# 06_JTAG_DBUG.net
KiCad netlist of a schematic drawn in Altium Designer
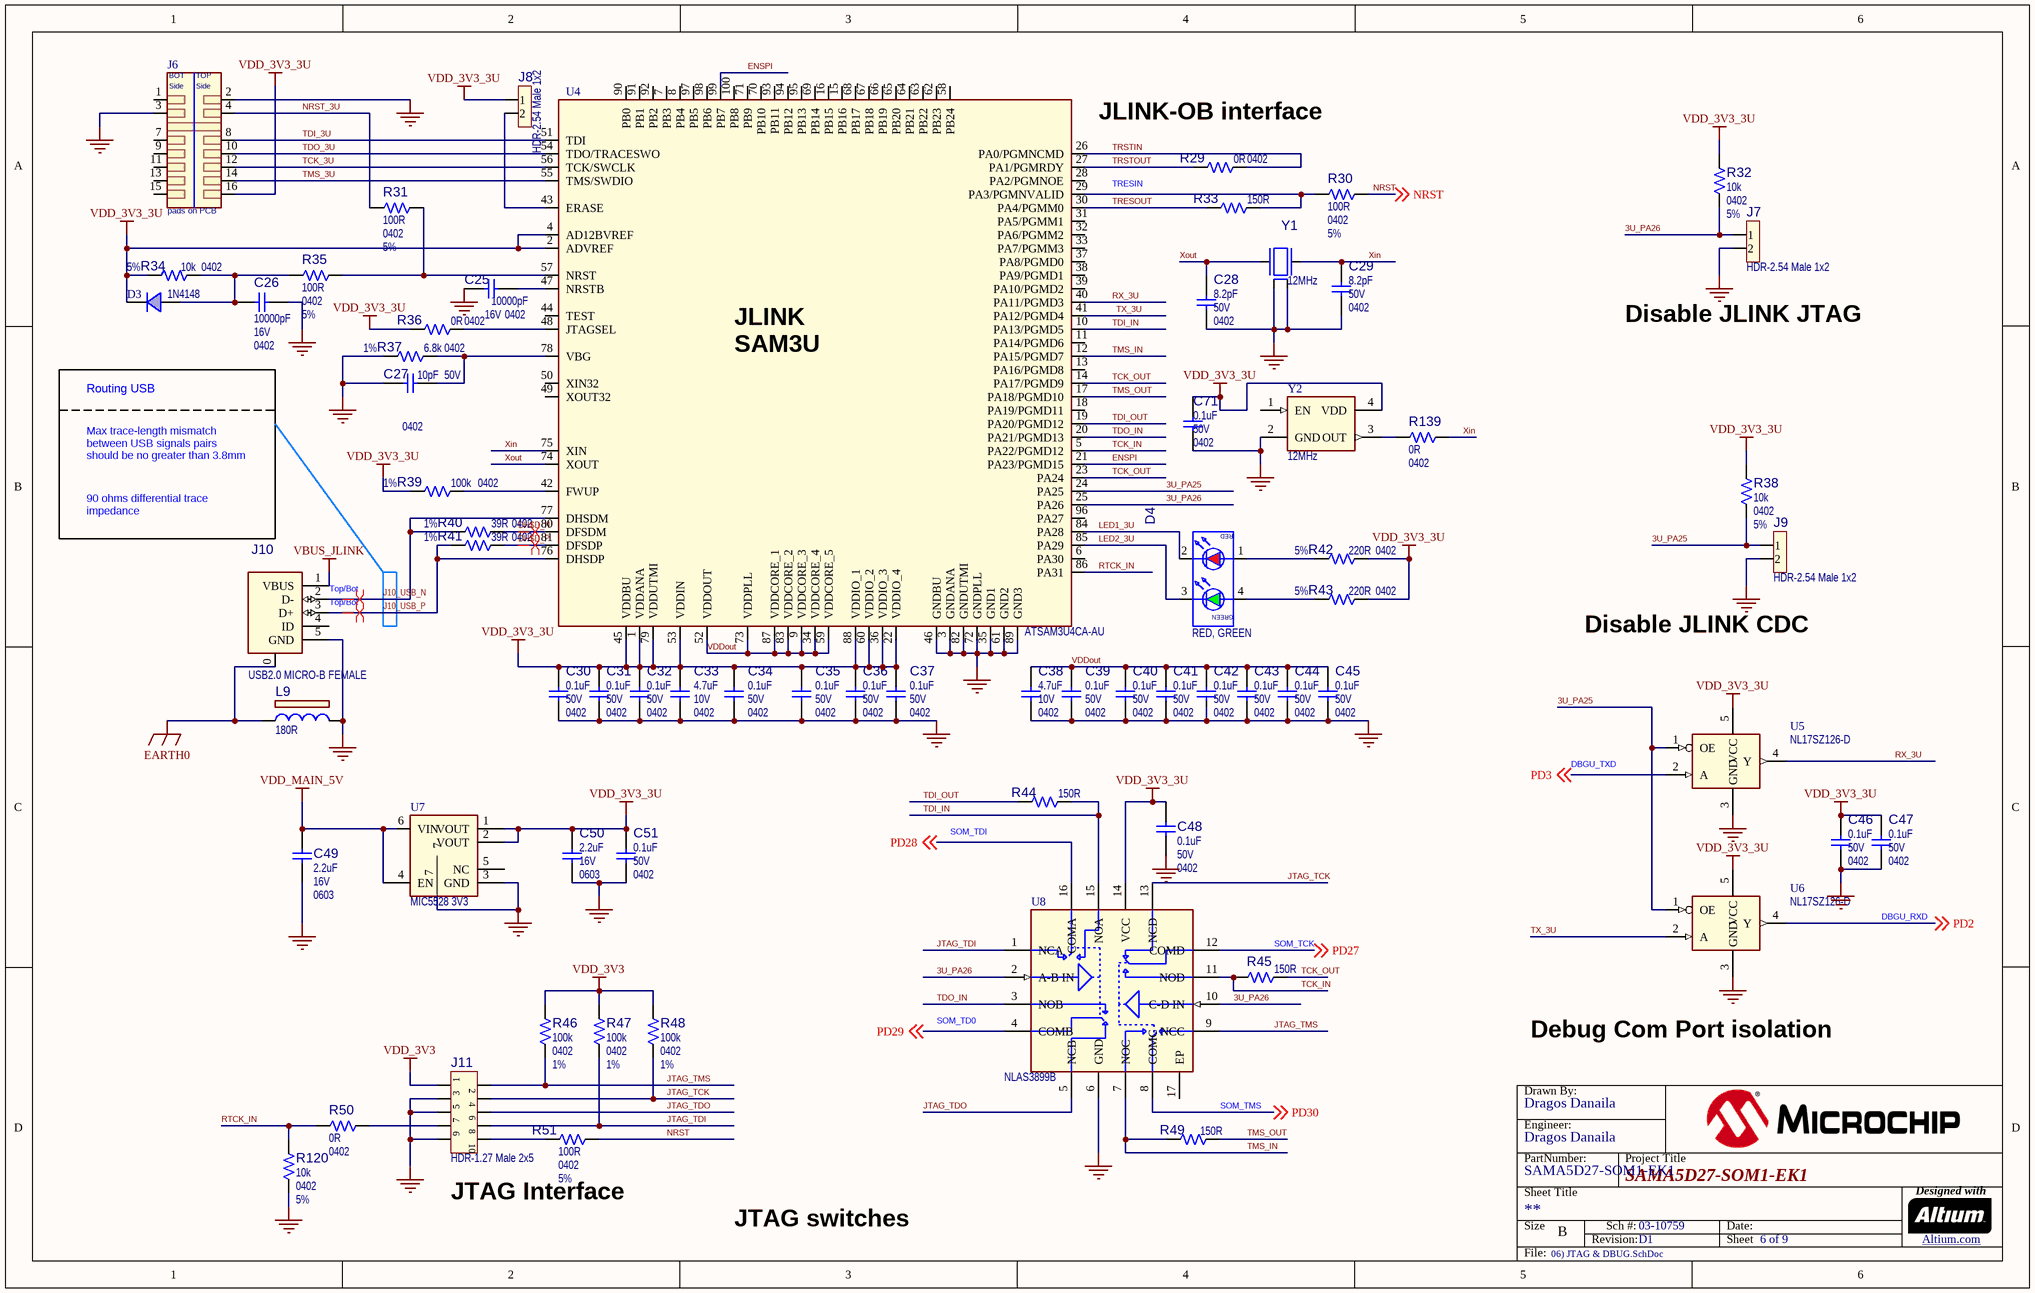
[diagram p0: 06) JTAG & DBUG.SchDoc]

(export (version "E")
  (design (tool "Eeschema 10.0.6"))
  (components
    (comp (ref "C25")
      (value "10000pF")
      (footprint "CAP_C_0402")
      (description "Capacitor")
      (fields
        (field (name "VOLTAGE") "16V")
        (field (name "PACKAGE") "0402")
        (field (name "TOLERANCE") "10%")
        (field (name "Comment") "Capacitor NP")
      )
      (libsource (lib "MCHP-CDB") (part "Capacitor NP"))
    )
    (comp (ref "C26")
      (value "10000pF")
      (footprint "CAP_C_0402")
      (description "Capacitor")
      (fields
        (field (name "VOLTAGE") "16V")
        (field (name "PACKAGE") "0402")
        (field (name "TOLERANCE") "10%")
        (field (name "Comment") "Capacitor NP")
      )
      (libsource (lib "MCHP-CDB") (part "Capacitor NP"))
    )
    (comp (ref "C27")
      (value "10pF")
      (footprint "CAP_C_0402")
      (description "Capacitor")
      (fields
        (field (name "VOLTAGE") "50V")
        (field (name "PACKAGE") "0402")
        (field (name "TOLERANCE") "5%")
        (field (name "Comment") "Capacitor NP")
      )
      (libsource (lib "MCHP-CDB") (part "Capacitor NP"))
    )
    (comp (ref "C28")
      (value "8.2pF")
      (footprint "CAP_C_0402")
      (description "Capacitor")
      (fields
        (field (name "VOLTAGE") "50V")
        (field (name "PACKAGE") "0402")
        (field (name "TOLERANCE") "0.25pF")
        (field (name "Comment") "Capacitor NP")
        (field (name "OWNER") "Gabor Bihari")
      )
      (libsource (lib "MCHP-CDB") (part "Capacitor NP"))
    )
    (comp (ref "C29")
      (value "8.2pF")
      (footprint "CAP_C_0402")
      (description "Capacitor")
      (fields
        (field (name "VOLTAGE") "50V")
        (field (name "PACKAGE") "0402")
        (field (name "TOLERANCE") "0.25pF")
        (field (name "Comment") "Capacitor NP")
        (field (name "OWNER") "Gabor Bihari")
      )
      (libsource (lib "MCHP-CDB") (part "Capacitor NP"))
    )
    (comp (ref "C30")
      (value "0.1uF")
      (footprint "CAP_C_0402")
      (description "Capacitor")
      (fields
        (field (name "VOLTAGE") "50V")
        (field (name "PACKAGE") "0402")
        (field (name "TOLERANCE") "10%")
        (field (name "Comment") "Capacitor NP")
        (field (name "OWNER") "Jamus Griego")
      )
      (libsource (lib "MCHP-CDB") (part "Capacitor NP"))
    )
    (comp (ref "C31")
      (value "0.1uF")
      (footprint "CAP_C_0402")
      (description "Capacitor")
      (fields
        (field (name "VOLTAGE") "50V")
        (field (name "PACKAGE") "0402")
        (field (name "TOLERANCE") "10%")
        (field (name "Comment") "Capacitor NP")
        (field (name "OWNER") "Jamus Griego")
      )
      (libsource (lib "MCHP-CDB") (part "Capacitor NP"))
    )
    (comp (ref "C32")
      (value "0.1uF")
      (footprint "CAP_C_0402")
      (description "Capacitor")
      (fields
        (field (name "VOLTAGE") "50V")
        (field (name "PACKAGE") "0402")
        (field (name "TOLERANCE") "10%")
        (field (name "Comment") "Capacitor NP")
        (field (name "OWNER") "Jamus Griego")
      )
      (libsource (lib "MCHP-CDB") (part "Capacitor NP"))
    )
    (comp (ref "C33")
      (value "4.7uF")
      (footprint "CAP_C_0402")
      (description "Capacitor")
      (fields
        (field (name "VOLTAGE") "10V")
        (field (name "PACKAGE") "0402")
        (field (name "TOLERANCE") "10%")
        (field (name "Comment") "Capacitor NP")
        (field (name "OWNER") "Jesus Aviles")
      )
      (libsource (lib "MCHP-CDB") (part "Capacitor NP"))
    )
    (comp (ref "C34")
      (value "0.1uF")
      (footprint "CAP_C_0402")
      (description "Capacitor")
      (fields
        (field (name "VOLTAGE") "50V")
        (field (name "PACKAGE") "0402")
        (field (name "TOLERANCE") "10%")
        (field (name "Comment") "Capacitor NP")
        (field (name "OWNER") "Jamus Griego")
      )
      (libsource (lib "MCHP-CDB") (part "Capacitor NP"))
    )
    (comp (ref "C35")
      (value "0.1uF")
      (footprint "CAP_C_0402")
      (description "Capacitor")
      (fields
        (field (name "VOLTAGE") "50V")
        (field (name "PACKAGE") "0402")
        (field (name "TOLERANCE") "10%")
        (field (name "Comment") "Capacitor NP")
        (field (name "OWNER") "Jamus Griego")
      )
      (libsource (lib "MCHP-CDB") (part "Capacitor NP"))
    )
    (comp (ref "C36")
      (value "0.1uF")
      (footprint "CAP_C_0402")
      (description "Capacitor")
      (fields
        (field (name "VOLTAGE") "50V")
        (field (name "PACKAGE") "0402")
        (field (name "TOLERANCE") "10%")
        (field (name "Comment") "Capacitor NP")
        (field (name "OWNER") "Jamus Griego")
      )
      (libsource (lib "MCHP-CDB") (part "Capacitor NP"))
    )
    (comp (ref "C37")
      (value "0.1uF")
      (footprint "CAP_C_0402")
      (description "Capacitor")
      (fields
        (field (name "VOLTAGE") "50V")
        (field (name "PACKAGE") "0402")
        (field (name "TOLERANCE") "10%")
        (field (name "Comment") "Capacitor NP")
        (field (name "OWNER") "Jamus Griego")
      )
      (libsource (lib "MCHP-CDB") (part "Capacitor NP"))
    )
    (comp (ref "C38")
      (value "4.7uF")
      (footprint "CAP_C_0402")
      (description "Capacitor")
      (fields
        (field (name "VOLTAGE") "10V")
        (field (name "PACKAGE") "0402")
        (field (name "TOLERANCE") "10%")
        (field (name "Comment") "Capacitor NP")
        (field (name "OWNER") "Jesus Aviles")
      )
      (libsource (lib "MCHP-CDB") (part "Capacitor NP"))
    )
    (comp (ref "C39")
      (value "0.1uF")
      (footprint "CAP_C_0402")
      (description "Capacitor")
      (fields
        (field (name "VOLTAGE") "50V")
        (field (name "PACKAGE") "0402")
        (field (name "TOLERANCE") "10%")
        (field (name "Comment") "Capacitor NP")
        (field (name "OWNER") "Jamus Griego")
      )
      (libsource (lib "MCHP-CDB") (part "Capacitor NP"))
    )
    (comp (ref "C40")
      (value "0.1uF")
      (footprint "CAP_C_0402")
      (description "Capacitor")
      (fields
        (field (name "VOLTAGE") "50V")
        (field (name "PACKAGE") "0402")
        (field (name "TOLERANCE") "10%")
        (field (name "Comment") "Capacitor NP")
        (field (name "OWNER") "Jamus Griego")
      )
      (libsource (lib "MCHP-CDB") (part "Capacitor NP"))
    )
    (comp (ref "C41")
      (value "0.1uF")
      (footprint "CAP_C_0402")
      (description "Capacitor")
      (fields
        (field (name "VOLTAGE") "50V")
        (field (name "PACKAGE") "0402")
        (field (name "TOLERANCE") "10%")
        (field (name "Comment") "Capacitor NP")
        (field (name "OWNER") "Jamus Griego")
      )
      (libsource (lib "MCHP-CDB") (part "Capacitor NP"))
    )
    (comp (ref "C42")
      (value "0.1uF")
      (footprint "CAP_C_0402")
      (description "Capacitor")
      (fields
        (field (name "VOLTAGE") "50V")
        (field (name "PACKAGE") "0402")
        (field (name "TOLERANCE") "10%")
        (field (name "Comment") "Capacitor NP")
        (field (name "OWNER") "Jamus Griego")
      )
      (libsource (lib "MCHP-CDB") (part "Capacitor NP"))
    )
    (comp (ref "C43")
      (value "0.1uF")
      (footprint "CAP_C_0402")
      (description "Capacitor")
      (fields
        (field (name "VOLTAGE") "50V")
        (field (name "PACKAGE") "0402")
        (field (name "TOLERANCE") "10%")
        (field (name "Comment") "Capacitor NP")
        (field (name "OWNER") "Jamus Griego")
      )
      (libsource (lib "MCHP-CDB") (part "Capacitor NP"))
    )
    (comp (ref "C44")
      (value "0.1uF")
      (footprint "CAP_C_0402")
      (description "Capacitor")
      (fields
        (field (name "VOLTAGE") "50V")
        (field (name "PACKAGE") "0402")
        (field (name "TOLERANCE") "10%")
        (field (name "Comment") "Capacitor NP")
        (field (name "OWNER") "Jamus Griego")
      )
      (libsource (lib "MCHP-CDB") (part "Capacitor NP"))
    )
    (comp (ref "C45")
      (value "0.1uF")
      (footprint "CAP_C_0402")
      (description "Capacitor")
      (fields
        (field (name "VOLTAGE") "50V")
        (field (name "PACKAGE") "0402")
        (field (name "TOLERANCE") "10%")
        (field (name "Comment") "Capacitor NP")
        (field (name "OWNER") "Jamus Griego")
      )
      (libsource (lib "MCHP-CDB") (part "Capacitor NP"))
    )
    (comp (ref "C46")
      (value "0.1uF")
      (footprint "CAP_C_0402")
      (description "Capacitor")
      (fields
        (field (name "VOLTAGE") "50V")
        (field (name "PACKAGE") "0402")
        (field (name "TOLERANCE") "10%")
        (field (name "Comment") "Capacitor NP")
        (field (name "OWNER") "Jamus Griego")
      )
      (libsource (lib "MCHP-CDB") (part "Capacitor NP"))
    )
    (comp (ref "C47")
      (value "0.1uF")
      (footprint "CAP_C_0402")
      (description "Capacitor")
      (fields
        (field (name "VOLTAGE") "50V")
        (field (name "PACKAGE") "0402")
        (field (name "TOLERANCE") "10%")
        (field (name "Comment") "Capacitor NP")
        (field (name "OWNER") "Jamus Griego")
      )
      (libsource (lib "MCHP-CDB") (part "Capacitor NP"))
    )
    (comp (ref "C48")
      (value "0.1uF")
      (footprint "CAP_C_0402")
      (description "Capacitor")
      (fields
        (field (name "VOLTAGE") "50V")
        (field (name "PACKAGE") "0402")
        (field (name "TOLERANCE") "10%")
        (field (name "Comment") "Capacitor NP")
        (field (name "OWNER") "Jamus Griego")
      )
      (libsource (lib "MCHP-CDB") (part "Capacitor NP"))
    )
    (comp (ref "C49")
      (value "2.2uF")
      (footprint "CAP_C_0603")
      (description "Capacitor")
      (fields
        (field (name "VOLTAGE") "16V")
        (field (name "PACKAGE") "0603")
        (field (name "TOLERANCE") "10%")
        (field (name "Comment") "Capacitor NP")
      )
      (libsource (lib "MCHP-CDB") (part "Capacitor NP"))
    )
    (comp (ref "C50")
      (value "2.2uF")
      (footprint "CAP_C_0603")
      (description "Capacitor")
      (fields
        (field (name "VOLTAGE") "16V")
        (field (name "PACKAGE") "0603")
        (field (name "TOLERANCE") "10%")
        (field (name "Comment") "Capacitor NP")
      )
      (libsource (lib "MCHP-CDB") (part "Capacitor NP"))
    )
    (comp (ref "C51")
      (value "0.1uF")
      (footprint "CAP_C_0402")
      (description "Capacitor")
      (fields
        (field (name "VOLTAGE") "50V")
        (field (name "PACKAGE") "0402")
        (field (name "TOLERANCE") "10%")
        (field (name "Comment") "Capacitor NP")
        (field (name "OWNER") "Jamus Griego")
      )
      (libsource (lib "MCHP-CDB") (part "Capacitor NP"))
    )
    (comp (ref "C71")
      (value "0.1uF")
      (footprint "CAP_C_0402")
      (description "Capacitor")
      (fields
        (field (name "VOLTAGE") "50V")
        (field (name "PACKAGE") "0402")
        (field (name "TOLERANCE") "10%")
        (field (name "Comment") "Capacitor NP")
        (field (name "OWNER") "Jamus Griego")
      )
      (libsource (lib "MCHP-CDB") (part "Capacitor NP"))
    )
    (comp (ref "D3")
      (value "1N4148")
      (footprint "SOD-323")
      (description "DIO RECT 1N4148 855mV 300mA 75V SOD-323")
      (fields (field (name "POWER") "200mW") (field (name "Comment") "Diode Single"))
      (libsource (lib "MCHP-CDB") (part "Diode Single"))
    )
    (comp (ref "D4")
      (value "RED, GREEN")
      (footprint "LED_DUAL_SMD_2x1.25mm")
      (description "LED")
      (fields
        (field (name "POWER") "75mW")
        (field (name "Comment") "LED DUAL 4 pin")
        (field (name "OWNER") "Bogdan P (M91398)")
      )
      (libsource (lib "MCHP-CDB") (part "LED DUAL 4 pin"))
    )
    (comp (ref "J6")
      (value "pads on PCB")
      (footprint "CON_EDGE-CARD_PCB_RA_MEC1-108-02-F-D-RA1-SL")
      (description "CON_PCB_MEC1-108-02-F-D-RA1-SL")
      (fields (field (name "OWNER") "Dragos Danaila"))
      (libsource (lib "MCHP-CDB") (part "CON_PCB_MEC1-108-02-F-D-RA1-SL"))
    )
    (comp (ref "J7")
      (value "HDR-2.54 Male 1x2")
      (footprint "HDR_M_2.54_1x2")
      (fields (field (name "Comment") "Header 1x2") (field (name "OWNER") "Bogdan P (M91398)"))
      (libsource (lib "MCHP-CDB") (part "Header 1x2"))
    )
    (comp (ref "J8")
      (value "HDR-2.54 Male 1x2")
      (footprint "HDR_M_2.54_1x2")
      (fields (field (name "Comment") "Header 1x2") (field (name "OWNER") "Bogdan P (M91398)"))
      (libsource (lib "MCHP-CDB") (part "Header 1x2"))
    )
    (comp (ref "J9")
      (value "HDR-2.54 Male 1x2")
      (footprint "HDR_M_2.54_1x2")
      (fields (field (name "Comment") "Header 1x2") (field (name "OWNER") "Bogdan P (M91398)"))
      (libsource (lib "MCHP-CDB") (part "Header 1x2"))
    )
    (comp (ref "J10")
      (value "USB2.0 MICRO-B FEMALE")
      (footprint "CON_USB_Micro-AB_SMD_TH_RA_FCI_10118194-0001LF")
      (description "Connector USB Mini")
      (fields (field (name "Comment") "CON USB2.0 Mini_Micro") (field (name "OWNER") "Jamus Griego"))
      (libsource (lib "MCHP-CDB") (part "CON USB2.0 Mini_Micro"))
    )
    (comp (ref "J11")
      (value "HDR-1.27 Male 2x5")
      (footprint "HDR_M_1.27_2x5_SMD_V_SAM_FTSH-105-01-F-DV-K")
      (description "CON HDR-1.27 Male 2x5 Gold 3.05MH SMD VERT")
      (fields (field (name "Comment") "Header 2x5") (field (name "OWNER") "Tad Ahlvers"))
      (libsource (lib "MCHP-CDB") (part "Header 2x5"))
    )
    (comp (ref "L9")
      (value "180R")
      (footprint "IND_C_0603")
      (description "FERRITE 180R 1.5A SMD 0603")
      (fields (field (name "Comment") "Ferrite Bead") (field (name "OWNER") "Dragos Danaila"))
      (libsource (lib "MCHP-CDB") (part "Ferrite Bead"))
    )
    (comp (ref "R29")
      (value "0R")
      (footprint "RES_C_0402")
      (description "Resistor")
      (fields (field (name "PACKAGE") "0402") (field (name "POWER") "1/10W"))
      (libsource (lib "MCHP-CDB") (part "Resistor"))
    )
    (comp (ref "R30")
      (value "100R")
      (footprint "RES_C_0402")
      (description "Resistor")
      (fields
        (field (name "PACKAGE") "0402")
        (field (name "TOLERANCE") "5%")
        (field (name "VOLTAGE") "50V")
        (field (name "POWER") "1/16W")
        (field (name "OWNER") "Sompoch Loboonlert")
      )
      (libsource (lib "MCHP-CDB") (part "Resistor"))
    )
    (comp (ref "R31")
      (value "100R")
      (footprint "RES_C_0402")
      (description "Resistor")
      (fields
        (field (name "PACKAGE") "0402")
        (field (name "TOLERANCE") "5%")
        (field (name "VOLTAGE") "50V")
        (field (name "POWER") "1/16W")
        (field (name "OWNER") "Sompoch Loboonlert")
      )
      (libsource (lib "MCHP-CDB") (part "Resistor"))
    )
    (comp (ref "R32")
      (value "10k")
      (footprint "RES_C_0402")
      (description "Resistor")
      (fields
        (field (name "PACKAGE") "0402")
        (field (name "TOLERANCE") "5%")
        (field (name "VOLTAGE") "50V")
        (field (name "POWER") "1/16W")
      )
      (libsource (lib "MCHP-CDB") (part "Resistor"))
    )
    (comp (ref "R33")
      (value "150R")
      (footprint "RES_C_0402")
      (description "Resistor")
      (fields (field (name "OWNER") "Jamus Griego"))
      (libsource (lib "MCHP-CDB") (part "Resistor"))
    )
    (comp (ref "R34")
      (value "10k")
      (footprint "RES_C_0402")
      (description "Resistor")
      (fields
        (field (name "PACKAGE") "0402")
        (field (name "TOLERANCE") "5%")
        (field (name "VOLTAGE") "50V")
        (field (name "POWER") "1/16W")
      )
      (libsource (lib "MCHP-CDB") (part "Resistor"))
    )
    (comp (ref "R35")
      (value "100R")
      (footprint "RES_C_0402")
      (description "Resistor")
      (fields
        (field (name "PACKAGE") "0402")
        (field (name "TOLERANCE") "5%")
        (field (name "VOLTAGE") "50V")
        (field (name "POWER") "1/16W")
        (field (name "OWNER") "Sompoch Loboonlert")
      )
      (libsource (lib "MCHP-CDB") (part "Resistor"))
    )
    (comp (ref "R36")
      (value "0R")
      (footprint "RES_C_0402")
      (description "Resistor")
      (fields (field (name "PACKAGE") "0402") (field (name "POWER") "1/10W"))
      (libsource (lib "MCHP-CDB") (part "Resistor"))
    )
    (comp (ref "R37")
      (value "6.8k")
      (footprint "RES_C_0402")
      (description "Resistor")
      (fields
        (field (name "PACKAGE") "0402")
        (field (name "TOLERANCE") "1%")
        (field (name "VOLTAGE") "50V")
        (field (name "POWER") "1/16W")
        (field (name "OWNER") "Dragos Danaila")
      )
      (libsource (lib "MCHP-CDB") (part "Resistor"))
    )
    (comp (ref "R38")
      (value "10k")
      (footprint "RES_C_0402")
      (description "Resistor")
      (fields
        (field (name "PACKAGE") "0402")
        (field (name "TOLERANCE") "5%")
        (field (name "VOLTAGE") "50V")
        (field (name "POWER") "1/16W")
      )
      (libsource (lib "MCHP-CDB") (part "Resistor"))
    )
    (comp (ref "R39")
      (value "100k")
      (footprint "RES_C_0402")
      (description "Resistor")
      (fields
        (field (name "PACKAGE") "0402")
        (field (name "TOLERANCE") "1%")
        (field (name "VOLTAGE") "50V")
        (field (name "POWER") "1/10W")
        (field (name "OWNER") "Tad Ahlvers")
      )
      (libsource (lib "MCHP-CDB") (part "Resistor"))
    )
    (comp (ref "R40")
      (value "39R")
      (footprint "RES_C_0402")
      (description "Resistor")
      (fields
        (field (name "PACKAGE") "0402")
        (field (name "TOLERANCE") "1%")
        (field (name "POWER") "1/16W")
        (field (name "OWNER") "Sompoch Loboonlert")
      )
      (libsource (lib "MCHP-CDB") (part "Resistor"))
    )
    (comp (ref "R41")
      (value "39R")
      (footprint "RES_C_0402")
      (description "Resistor")
      (fields
        (field (name "PACKAGE") "0402")
        (field (name "TOLERANCE") "1%")
        (field (name "POWER") "1/16W")
        (field (name "OWNER") "Sompoch Loboonlert")
      )
      (libsource (lib "MCHP-CDB") (part "Resistor"))
    )
    (comp (ref "R42")
      (value "220R")
      (footprint "RES_C_0402")
      (description "Resistor")
      (fields
        (field (name "PACKAGE") "0402")
        (field (name "TOLERANCE") "5%")
        (field (name "VOLTAGE") "50V")
        (field (name "POWER") "1/10W")
        (field (name "OWNER") "Tad Ahlvers")
      )
      (libsource (lib "MCHP-CDB") (part "Resistor"))
    )
    (comp (ref "R43")
      (value "220R")
      (footprint "RES_C_0402")
      (description "Resistor")
      (fields
        (field (name "PACKAGE") "0402")
        (field (name "TOLERANCE") "5%")
        (field (name "VOLTAGE") "50V")
        (field (name "POWER") "1/10W")
        (field (name "OWNER") "Tad Ahlvers")
      )
      (libsource (lib "MCHP-CDB") (part "Resistor"))
    )
    (comp (ref "R44")
      (value "150R")
      (footprint "RES_C_0402")
      (description "Resistor")
      (fields (field (name "OWNER") "Jamus Griego"))
      (libsource (lib "MCHP-CDB") (part "Resistor"))
    )
    (comp (ref "R45")
      (value "150R")
      (footprint "RES_C_0402")
      (description "Resistor")
      (fields (field (name "OWNER") "Jamus Griego"))
      (libsource (lib "MCHP-CDB") (part "Resistor"))
    )
    (comp (ref "R46")
      (value "100k")
      (footprint "RES_C_0402")
      (description "Resistor")
      (fields
        (field (name "PACKAGE") "0402")
        (field (name "TOLERANCE") "1%")
        (field (name "VOLTAGE") "50V")
        (field (name "POWER") "1/10W")
        (field (name "OWNER") "Tad Ahlvers")
      )
      (libsource (lib "MCHP-CDB") (part "Resistor"))
    )
    (comp (ref "R47")
      (value "100k")
      (footprint "RES_C_0402")
      (description "Resistor")
      (fields
        (field (name "PACKAGE") "0402")
        (field (name "TOLERANCE") "1%")
        (field (name "VOLTAGE") "50V")
        (field (name "POWER") "1/10W")
        (field (name "OWNER") "Tad Ahlvers")
      )
      (libsource (lib "MCHP-CDB") (part "Resistor"))
    )
    (comp (ref "R48")
      (value "100k")
      (footprint "RES_C_0402")
      (description "Resistor")
      (fields
        (field (name "PACKAGE") "0402")
        (field (name "TOLERANCE") "1%")
        (field (name "VOLTAGE") "50V")
        (field (name "POWER") "1/10W")
        (field (name "OWNER") "Tad Ahlvers")
      )
      (libsource (lib "MCHP-CDB") (part "Resistor"))
    )
    (comp (ref "R49")
      (value "150R")
      (footprint "RES_C_0402")
      (description "Resistor")
      (fields (field (name "OWNER") "Jamus Griego"))
      (libsource (lib "MCHP-CDB") (part "Resistor"))
    )
    (comp (ref "R50")
      (value "0R")
      (footprint "RES_C_0402")
      (description "Resistor")
      (fields (field (name "PACKAGE") "0402") (field (name "POWER") "1/10W"))
      (libsource (lib "MCHP-CDB") (part "Resistor"))
    )
    (comp (ref "R51")
      (value "100R")
      (footprint "RES_C_0402")
      (description "Resistor")
      (fields
        (field (name "PACKAGE") "0402")
        (field (name "TOLERANCE") "5%")
        (field (name "VOLTAGE") "50V")
        (field (name "POWER") "1/16W")
        (field (name "OWNER") "Sompoch Loboonlert")
      )
      (libsource (lib "MCHP-CDB") (part "Resistor"))
    )
    (comp (ref "R120")
      (value "10k")
      (footprint "RES_C_0402")
      (description "Resistor")
      (fields
        (field (name "PACKAGE") "0402")
        (field (name "TOLERANCE") "5%")
        (field (name "VOLTAGE") "50V")
        (field (name "POWER") "1/16W")
      )
      (libsource (lib "MCHP-CDB") (part "Resistor"))
    )
    (comp (ref "R139")
      (value "0R")
      (footprint "RES_C_0402")
      (description "Resistor")
      (fields (field (name "PACKAGE") "0402") (field (name "POWER") "1/10W"))
      (libsource (lib "MCHP-CDB") (part "Resistor"))
    )
    (comp (ref "U4")
      (value "ATSAM3U4CA-AU")
      (footprint "LQFP-100_14x14")
      (fields
        (field (name "Comment") "ATSAM3U4CA-AU LQFP-100")
        (field (name "OWNER") "Alexandru Chiser - M19201")
      )
      (libsource (lib "MCHP-CDB") (part "ATSAM3U4CA-AU LQFP-100"))
    )
    (comp (ref "U5")
      (value "NL17SZ126-D")
      (footprint "SOT-353")
      (fields
        (field (name "Comment") "NL17SZ126-D SOT-353")
        (field (name "OWNER") "Alexandru Chiser - M19201")
      )
      (libsource (lib "MCHP-CDB") (part "NL17SZ126-D SOT-353"))
    )
    (comp (ref "U6")
      (value "NL17SZ126-D")
      (footprint "SOT-353")
      (fields
        (field (name "Comment") "NL17SZ126-D SOT-353")
        (field (name "OWNER") "Alexandru Chiser - M19201")
      )
      (libsource (lib "MCHP-CDB") (part "NL17SZ126-D SOT-353"))
    )
    (comp (ref "U7")
      (value "MIC5528 3V3")
      (footprint "DFN-6_1.2x1.2")
      (fields (field (name "Comment") "MIC5528MT DFN-6") (field (name "OWNER") "Tim Moffat"))
      (libsource (lib "MCHP-CDB") (part "MIC5528MT DFN-6"))
    )
    (comp (ref "U8")
      (value "NLAS3899B")
      (footprint "QFN-16_3X3_EP1.4X1.4")
      (description "IC SWITCHER NLAS3899B Analog Switch QFN16")
      (fields (field (name "Comment") "NLAS3899B QFN16") (field (name "OWNER") "Dragos Danaila"))
      (libsource (lib "MCHP-CDB") (part "NLAS3899B QFN16"))
    )
    (comp (ref "Y1")
      (value "12MHz")
      (footprint "CRYSTAL_L7.5W5.2H1.4")
      (description "Crystal")
      (fields
        (field (name "TOLERANCE") "30ppm")
        (field (name "Comment") "Crystal 4 Pins")
        (field (name "OWNER") "Dragos Danaila")
      )
      (libsource (lib "MCHP-CDB") (part "Crystal 4 Pins"))
    )
    (comp (ref "Y2")
      (value "12MHz")
      (footprint "OSCILLATOR_ASE")
      (description "OSCILLATOR 12MHz 3.3V SMD ASE")
      (fields
        (field (name "VOLTAGE") "3.3V")
        (field (name "TOLERANCE") "50ppm")
        (field (name "OWNER") "Dragos Danaila")
      )
      (libsource (lib "MCHP-CDB") (part "OSCILLATOR 4 Pins"))
    )
  )
  (nets
    (net (code "1") (name "/3U_PA25") (class "Default")
      (node (ref "J9") (pin "1") (pinfunction "1_1") (pintype "passive"))
      (node (ref "R38") (pin "2") (pinfunction "2_2") (pintype "passive"))
      (node (ref "U4") (pin "24") (pinfunction "PA25_24") (pintype "passive"))
      (node (ref "U5") (pin "1") (pinfunction "OE_1") (pintype "input"))
      (node (ref "U6") (pin "1") (pinfunction "OE_1") (pintype "input"))
    )
    (net (code "2") (name "/3U_PA26") (class "Default")
      (node (ref "J7") (pin "1") (pinfunction "1_1") (pintype "passive"))
      (node (ref "R32") (pin "2") (pinfunction "2_2") (pintype "passive"))
      (node (ref "U4") (pin "25") (pinfunction "PA26_25") (pintype "passive"))
      (node (ref "U8") (pin "10") (pinfunction "C-D_IN_10") (pintype "input"))
      (node (ref "U8") (pin "2") (pinfunction "A-B_IN_2") (pintype "input"))
    )
    (net (code "3") (name "/DHSD_N") (class "Default")
      (node (ref "R40") (pin "2") (pinfunction "2_2") (pintype "passive"))
      (node (ref "U4") (pin "80") (pinfunction "DFSDM_80") (pintype "passive"))
    )
    (net (code "4") (name "/DHSD_P") (class "Default")
      (node (ref "R41") (pin "2") (pinfunction "2_2") (pintype "passive"))
      (node (ref "U4") (pin "81") (pinfunction "DFSDP_81") (pintype "passive"))
    )
    (net (code "5") (name "/ENSPI") (class "Default")
      (node (ref "U4") (pin "21") (pinfunction "PA23/PGMD15_21") (pintype "passive"))
      (node (ref "U4") (pin "99") (pinfunction "PB7_99") (pintype "passive"))
    )
    (net (code "6") (name "/J10_USB_N") (class "Default")
      (node (ref "J10") (pin "2") (pinfunction "D-_2") (pintype "bidirectional"))
      (node (ref "R40") (pin "1") (pinfunction "1_1") (pintype "passive"))
      (node (ref "U4") (pin "77") (pinfunction "DHSDM_77") (pintype "passive"))
    )
    (net (code "7") (name "/J10_USB_P") (class "Default")
      (node (ref "J10") (pin "3") (pinfunction "D+_3") (pintype "bidirectional"))
      (node (ref "R41") (pin "1") (pinfunction "1_1") (pintype "passive"))
      (node (ref "U4") (pin "76") (pinfunction "DHSDP_76") (pintype "passive"))
    )
    (net (code "8") (name "/JTAG_TCK") (class "Default")
      (node (ref "J11") (pin "4") (pinfunction "4_4") (pintype "passive"))
      (node (ref "R48") (pin "2") (pinfunction "2_2") (pintype "passive"))
      (node (ref "U8") (pin "13") (pinfunction "NCD_13") (pintype "passive"))
    )
    (net (code "9") (name "/JTAG_TDI") (class "Default")
      (node (ref "J11") (pin "8") (pinfunction "8_8") (pintype "passive"))
      (node (ref "R47") (pin "2") (pinfunction "2_2") (pintype "passive"))
      (node (ref "U8") (pin "1") (pinfunction "NCA_1") (pintype "passive"))
    )
    (net (code "10") (name "/JTAG_TDO") (class "Default")
      (node (ref "J11") (pin "6") (pinfunction "6_6") (pintype "passive"))
      (node (ref "U8") (pin "5") (pinfunction "NCB_5") (pintype "passive"))
    )
    (net (code "11") (name "/JTAG_TMS") (class "Default")
      (node (ref "J11") (pin "2") (pinfunction "2_2") (pintype "passive"))
      (node (ref "R46") (pin "2") (pinfunction "2_2") (pintype "passive"))
      (node (ref "U8") (pin "9") (pinfunction "NCC_9") (pintype "passive"))
    )
    (net (code "12") (name "/LED1_3U") (class "Default")
      (node (ref "D4") (pin "2") (pinfunction "K1_2") (pintype "passive"))
      (node (ref "U4") (pin "84") (pinfunction "PA28_84") (pintype "passive"))
    )
    (net (code "13") (name "/LED2_3U") (class "Default")
      (node (ref "D4") (pin "3") (pinfunction "K2_3") (pintype "passive"))
      (node (ref "U4") (pin "85") (pinfunction "PA29_85") (pintype "passive"))
    )
    (net (code "14") (name "/NRST_3U") (class "Default")
      (node (ref "J6") (pin "4") (pinfunction "4_4") (pintype "passive"))
      (node (ref "R31") (pin "1") (pinfunction "1_1") (pintype "passive"))
    )
    (net (code "15") (name "/RTCK_IN") (class "Default")
      (node (ref "R120") (pin "1") (pinfunction "1_1") (pintype "passive"))
      (node (ref "R50") (pin "1") (pinfunction "1_1") (pintype "passive"))
      (node (ref "U4") (pin "86") (pinfunction "PA31_86") (pintype "passive"))
    )
    (net (code "16") (name "/RX_3U") (class "Default")
      (node (ref "U4") (pin "40") (pinfunction "PA11/PGMD3_40") (pintype "passive"))
      (node (ref "U5") (pin "4") (pinfunction "Y_4") (pintype "output"))
    )
    (net (code "17") (name "/TCK_3U") (class "Default")
      (node (ref "J6") (pin "12") (pinfunction "12_12") (pintype "passive"))
      (node (ref "U4") (pin "56") (pinfunction "TCK/SWCLK_56") (pintype "passive"))
    )
    (net (code "18") (name "/TCK_IN") (class "Default")
      (node (ref "R45") (pin "1") (pinfunction "1_1") (pintype "passive"))
      (node (ref "U4") (pin "5") (pinfunction "PA22/PGMD12_5") (pintype "passive"))
      (node (ref "U8") (pin "11") (pinfunction "NOD_11") (pintype "passive"))
    )
    (net (code "19") (name "/TCK_OUT") (class "Default")
      (node (ref "R45") (pin "2") (pinfunction "2_2") (pintype "passive"))
      (node (ref "U4") (pin "14") (pinfunction "PA17/PGMD9_14") (pintype "passive"))
      (node (ref "U4") (pin "23") (pinfunction "PA24_23") (pintype "passive"))
    )
    (net (code "20") (name "/TDI_3U") (class "Default")
      (node (ref "J6") (pin "8") (pinfunction "8_8") (pintype "passive"))
      (node (ref "U4") (pin "51") (pinfunction "TDI_51") (pintype "passive"))
    )
    (net (code "21") (name "/TDI_IN") (class "Default")
      (node (ref "R44") (pin "2") (pinfunction "2_2") (pintype "passive"))
      (node (ref "U4") (pin "10") (pinfunction "PA13/PGMD5_10") (pintype "passive"))
      (node (ref "U8") (pin "15") (pinfunction "NOA_15") (pintype "passive"))
    )
    (net (code "22") (name "/TDI_OUT") (class "Default")
      (node (ref "R44") (pin "1") (pinfunction "1_1") (pintype "passive"))
      (node (ref "U4") (pin "19") (pinfunction "PA20/PGMD12_19") (pintype "passive"))
    )
    (net (code "23") (name "/TDO_3U") (class "Default")
      (node (ref "J6") (pin "10") (pinfunction "10_10") (pintype "passive"))
      (node (ref "U4") (pin "54") (pinfunction "TDO/TRACESWO_54") (pintype "passive"))
    )
    (net (code "24") (name "/TDO_IN") (class "Default")
      (node (ref "U4") (pin "20") (pinfunction "PA21/PGMD13_20") (pintype "passive"))
      (node (ref "U8") (pin "3") (pinfunction "NOB_3") (pintype "passive"))
    )
    (net (code "25") (name "/TMS_3U") (class "Default")
      (node (ref "J6") (pin "14") (pinfunction "14_14") (pintype "passive"))
      (node (ref "U4") (pin "55") (pinfunction "TMS/SWDIO_55") (pintype "passive"))
    )
    (net (code "26") (name "/TMS_IN") (class "Default")
      (node (ref "R49") (pin "1") (pinfunction "1_1") (pintype "passive"))
      (node (ref "U4") (pin "12") (pinfunction "PA15/PGMD7_12") (pintype "passive"))
      (node (ref "U8") (pin "7") (pinfunction "NOC_7") (pintype "passive"))
    )
    (net (code "27") (name "/TMS_OUT") (class "Default")
      (node (ref "R49") (pin "2") (pinfunction "2_2") (pintype "passive"))
      (node (ref "U4") (pin "17") (pinfunction "PA18/PGMD10_17") (pintype "passive"))
    )
    (net (code "28") (name "/TRESOUT") (class "Default")
      (node (ref "R33") (pin "1") (pinfunction "1_1") (pintype "passive"))
      (node (ref "U4") (pin "30") (pinfunction "PA4/PGMM0_30") (pintype "passive"))
    )
    (net (code "29") (name "/TRSTIN") (class "Default")
      (node (ref "R29") (pin "2") (pinfunction "2_2") (pintype "passive"))
      (node (ref "U4") (pin "26") (pinfunction "PA0/PGMNCMD_26") (pintype "passive"))
    )
    (net (code "30") (name "/TRSTOUT") (class "Default")
      (node (ref "R29") (pin "1") (pinfunction "1_1") (pintype "passive"))
      (node (ref "U4") (pin "27") (pinfunction "PA1/PGMRDY_27") (pintype "passive"))
    )
    (net (code "31") (name "/TX_3U") (class "Default")
      (node (ref "U4") (pin "41") (pinfunction "PA12/PGMD4_41") (pintype "passive"))
      (node (ref "U6") (pin "2") (pinfunction "A_2") (pintype "input"))
    )
    (net (code "32") (name "/VDDout") (class "Default")
      (node (ref "C38") (pin "1") (pinfunction "1_1") (pintype "passive"))
      (node (ref "C39") (pin "1") (pinfunction "1_1") (pintype "passive"))
      (node (ref "C40") (pin "1") (pinfunction "1_1") (pintype "passive"))
      (node (ref "C41") (pin "1") (pinfunction "1_1") (pintype "passive"))
      (node (ref "C42") (pin "1") (pinfunction "1_1") (pintype "passive"))
      (node (ref "C43") (pin "1") (pinfunction "1_1") (pintype "passive"))
      (node (ref "C44") (pin "1") (pinfunction "1_1") (pintype "passive"))
      (node (ref "C45") (pin "1") (pinfunction "1_1") (pintype "passive"))
      (node (ref "U4") (pin "34") (pinfunction "VDDCORE_4_34") (pintype "passive"))
      (node (ref "U4") (pin "52") (pinfunction "VDDOUT_52") (pintype "passive"))
      (node (ref "U4") (pin "59") (pinfunction "VDDCORE_5_59") (pintype "passive"))
      (node (ref "U4") (pin "73") (pinfunction "VDDPLL_73") (pintype "passive"))
      (node (ref "U4") (pin "83") (pinfunction "VDDCORE_2_83") (pintype "passive"))
      (node (ref "U4") (pin "87") (pinfunction "VDDCORE_1_87") (pintype "passive"))
      (node (ref "U4") (pin "9") (pinfunction "VDDCORE_3_9") (pintype "passive"))
    )
    (net (code "33") (name "/Xin") (class "Default")
      (node (ref "C29") (pin "1") (pinfunction "1_1") (pintype "passive"))
      (node (ref "R139") (pin "2") (pinfunction "2_2") (pintype "passive"))
      (node (ref "U4") (pin "75") (pinfunction "XIN_75") (pintype "passive"))
      (node (ref "Y1") (pin "3") (pinfunction "Osc2_3") (pintype "passive"))
    )
    (net (code "34") (name "/Xout") (class "Default")
      (node (ref "C28") (pin "1") (pinfunction "1_1") (pintype "passive"))
      (node (ref "U4") (pin "74") (pinfunction "XOUT_74") (pintype "passive"))
      (node (ref "Y1") (pin "1") (pinfunction "Osc1_1") (pintype "passive"))
    )
    (net (code "35") (name "EARTH0") (class "Default")
      (node (ref "J10") (pin "0") (pinfunction "SHLD_0") (pintype "passive"))
      (node (ref "L9") (pin "1") (pinfunction "1_1") (pintype "passive"))
    )
    (net (code "36") (name "GND_POWER") (class "Default")
      (node (ref "C25") (pin "1") (pinfunction "1_1") (pintype "passive"))
      (node (ref "C26") (pin "2") (pinfunction "2_2") (pintype "passive"))
      (node (ref "C27") (pin "2") (pinfunction "2_2") (pintype "passive"))
      (node (ref "C28") (pin "2") (pinfunction "2_2") (pintype "passive"))
      (node (ref "C29") (pin "2") (pinfunction "2_2") (pintype "passive"))
      (node (ref "C30") (pin "2") (pinfunction "2_2") (pintype "passive"))
      (node (ref "C31") (pin "2") (pinfunction "2_2") (pintype "passive"))
      (node (ref "C32") (pin "2") (pinfunction "2_2") (pintype "passive"))
      (node (ref "C33") (pin "2") (pinfunction "2_2") (pintype "passive"))
      (node (ref "C34") (pin "2") (pinfunction "2_2") (pintype "passive"))
      (node (ref "C35") (pin "2") (pinfunction "2_2") (pintype "passive"))
      (node (ref "C36") (pin "2") (pinfunction "2_2") (pintype "passive"))
      (node (ref "C37") (pin "2") (pinfunction "2_2") (pintype "passive"))
      (node (ref "C38") (pin "2") (pinfunction "2_2") (pintype "passive"))
      (node (ref "C39") (pin "2") (pinfunction "2_2") (pintype "passive"))
      (node (ref "C40") (pin "2") (pinfunction "2_2") (pintype "passive"))
      (node (ref "C41") (pin "2") (pinfunction "2_2") (pintype "passive"))
      (node (ref "C42") (pin "2") (pinfunction "2_2") (pintype "passive"))
      (node (ref "C43") (pin "2") (pinfunction "2_2") (pintype "passive"))
      (node (ref "C44") (pin "2") (pinfunction "2_2") (pintype "passive"))
      (node (ref "C45") (pin "2") (pinfunction "2_2") (pintype "passive"))
      (node (ref "C46") (pin "2") (pinfunction "2_2") (pintype "passive"))
      (node (ref "C47") (pin "2") (pinfunction "2_2") (pintype "passive"))
      (node (ref "C48") (pin "2") (pinfunction "2_2") (pintype "passive"))
      (node (ref "C49") (pin "2") (pinfunction "2_2") (pintype "passive"))
      (node (ref "C50") (pin "2") (pinfunction "2_2") (pintype "passive"))
      (node (ref "C51") (pin "2") (pinfunction "2_2") (pintype "passive"))
      (node (ref "C71") (pin "2") (pinfunction "2_2") (pintype "passive"))
      (node (ref "J10") (pin "5") (pinfunction "GND_5") (pintype "power_in"))
      (node (ref "J11") (pin "3") (pinfunction "3_3") (pintype "passive"))
      (node (ref "J11") (pin "5") (pinfunction "5_5") (pintype "passive"))
      (node (ref "J11") (pin "9") (pinfunction "9_9") (pintype "passive"))
      (node (ref "J6") (pin "2") (pinfunction "2_2") (pintype "passive"))
      (node (ref "J6") (pin "3") (pinfunction "3_3") (pintype "passive"))
      (node (ref "J7") (pin "2") (pinfunction "2_2") (pintype "passive"))
      (node (ref "J9") (pin "2") (pinfunction "2_2") (pintype "passive"))
      (node (ref "L9") (pin "2") (pinfunction "2_2") (pintype "passive"))
      (node (ref "R120") (pin "2") (pinfunction "2_2") (pintype "passive"))
      (node (ref "R37") (pin "1") (pinfunction "1_1") (pintype "passive"))
      (node (ref "U4") (pin "3") (pinfunction "GNDANA_3") (pintype "passive"))
      (node (ref "U4") (pin "35") (pinfunction "GND1_35") (pintype "power_in"))
      (node (ref "U4") (pin "46") (pinfunction "GNDBU_46") (pintype "passive"))
      (node (ref "U4") (pin "61") (pinfunction "GND2_61") (pintype "power_in"))
      (node (ref "U4") (pin "72") (pinfunction "GNDPLL_72") (pintype "passive"))
      (node (ref "U4") (pin "82") (pinfunction "GNDUTMI_82") (pintype "passive"))
      (node (ref "U4") (pin "89") (pinfunction "GND3_89") (pintype "power_in"))
      (node (ref "U5") (pin "3") (pinfunction "GND_3") (pintype "passive"))
      (node (ref "U6") (pin "3") (pinfunction "GND_3") (pintype "passive"))
      (node (ref "U7") (pin "3") (pinfunction "GND_3") (pintype "passive"))
      (node (ref "U7") (pin "7") (pinfunction "7_7") (pintype "passive"))
      (node (ref "U8") (pin "6") (pinfunction "GND_6") (pintype "power_in"))
      (node (ref "Y1") (pin "2") (pinfunction "GND_2") (pintype "power_in"))
      (node (ref "Y1") (pin "4") (pinfunction "GND_4") (pintype "power_in"))
      (node (ref "Y2") (pin "2") (pinfunction "GND_2") (pintype "power_in"))
    )
    (net (code "37") (name "NRST") (class "Default")
      (node (ref "R30") (pin "2") (pinfunction "2_2") (pintype "passive"))
      (node (ref "R51") (pin "2") (pinfunction "2_2") (pintype "passive"))
    )
    (net (code "38") (name "Net-(D3-A)") (class "Default")
      (node (ref "C26") (pin "1") (pinfunction "1_1") (pintype "passive"))
      (node (ref "D3") (pin "1") (pinfunction "A_1") (pintype "passive"))
      (node (ref "R34") (pin "2") (pinfunction "2_2") (pintype "passive"))
      (node (ref "R35") (pin "1") (pinfunction "1_1") (pintype "passive"))
    )
    (net (code "39") (name "Net-(D4-A1)") (class "Default")
      (node (ref "D4") (pin "1") (pinfunction "A1_1") (pintype "passive"))
      (node (ref "R42") (pin "1") (pinfunction "1_1") (pintype "passive"))
    )
    (net (code "40") (name "Net-(D4-A2)") (class "Default")
      (node (ref "D4") (pin "4") (pinfunction "A2_4") (pintype "passive"))
      (node (ref "R43") (pin "1") (pinfunction "1_1") (pintype "passive"))
    )
    (net (code "41") (name "Net-(J11-Pad7)") (class "Default")
      (node (ref "J11") (pin "7") (pinfunction "7_7") (pintype "passive"))
      (node (ref "R50") (pin "2") (pinfunction "2_2") (pintype "passive"))
    )
    (net (code "42") (name "Net-(J11-Pad10)") (class "Default")
      (node (ref "J11") (pin "10") (pinfunction "10_10") (pintype "passive"))
      (node (ref "R51") (pin "1") (pinfunction "1_1") (pintype "passive"))
    )
    (net (code "43") (name "Net-(U4-ERASE)") (class "Default")
      (node (ref "J8") (pin "2") (pinfunction "2_2") (pintype "passive"))
      (node (ref "U4") (pin "43") (pinfunction "ERASE_43") (pintype "passive"))
    )
    (net (code "44") (name "Net-(U4-FWUP)") (class "Default")
      (node (ref "R39") (pin "2") (pinfunction "2_2") (pintype "passive"))
      (node (ref "U4") (pin "42") (pinfunction "FWUP_42") (pintype "passive"))
    )
    (net (code "45") (name "Net-(U4-JTAGSEL)") (class "Default")
      (node (ref "R36") (pin "2") (pinfunction "2_2") (pintype "passive"))
      (node (ref "U4") (pin "48") (pinfunction "JTAGSEL_48") (pintype "passive"))
    )
    (net (code "46") (name "Net-(U4-NRST)") (class "Default")
      (node (ref "R31") (pin "2") (pinfunction "2_2") (pintype "passive"))
      (node (ref "R35") (pin "2") (pinfunction "2_2") (pintype "passive"))
      (node (ref "U4") (pin "57") (pinfunction "NRST_57") (pintype "passive"))
    )
    (net (code "47") (name "Net-(U4-NRSTB)") (class "Default")
      (node (ref "C25") (pin "2") (pinfunction "2_2") (pintype "passive"))
      (node (ref "U4") (pin "47") (pinfunction "NRSTB_47") (pintype "passive"))
    )
    (net (code "48") (name "Net-(U4-PA3{slash}PGMNVALID)") (class "Default")
      (node (ref "R30") (pin "1") (pinfunction "1_1") (pintype "passive"))
      (node (ref "R33") (pin "2") (pinfunction "2_2") (pintype "passive"))
      (node (ref "U4") (pin "29") (pinfunction "PA3/PGMNVALID_29") (pintype "passive"))
    )
    (net (code "49") (name "Net-(U4-VBG)") (class "Default")
      (node (ref "C27") (pin "1") (pinfunction "1_1") (pintype "passive"))
      (node (ref "R37") (pin "2") (pinfunction "2_2") (pintype "passive"))
      (node (ref "U4") (pin "78") (pinfunction "VBG_78") (pintype "passive"))
    )
    (net (code "50") (name "Net-(Y2-OUT)") (class "Default")
      (node (ref "R139") (pin "1") (pinfunction "1_1") (pintype "passive"))
      (node (ref "Y2") (pin "3") (pinfunction "OUT_3") (pintype "output"))
    )
    (net (code "51") (name "PD2") (class "Default")
      (node (ref "U6") (pin "4") (pinfunction "Y_4") (pintype "output"))
    )
    (net (code "52") (name "PD3") (class "Default")
      (node (ref "U5") (pin "2") (pinfunction "A_2") (pintype "input"))
    )
    (net (code "53") (name "PD27") (class "Default")
      (node (ref "U8") (pin "12") (pinfunction "COMD_12") (pintype "passive"))
    )
    (net (code "54") (name "PD28") (class "Default")
      (node (ref "U8") (pin "16") (pinfunction "COMA_16") (pintype "passive"))
    )
    (net (code "55") (name "PD29") (class "Default")
      (node (ref "U8") (pin "4") (pinfunction "COMB_4") (pintype "passive"))
    )
    (net (code "56") (name "PD30") (class "Default")
      (node (ref "U8") (pin "8") (pinfunction "COMC_8") (pintype "passive"))
    )
    (net (code "57") (name "VBUS_JLINK") (class "Default")
      (node (ref "J10") (pin "1") (pinfunction "VBUS_1") (pintype "power_in"))
    )
    (net (code "58") (name "VDD_3V3") (class "Default")
      (node (ref "J11") (pin "1") (pinfunction "1_1") (pintype "passive"))
      (node (ref "R46") (pin "1") (pinfunction "1_1") (pintype "passive"))
      (node (ref "R47") (pin "1") (pinfunction "1_1") (pintype "passive"))
      (node (ref "R48") (pin "1") (pinfunction "1_1") (pintype "passive"))
    )
    (net (code "59") (name "VDD_3V3_3U") (class "Default")
      (node (ref "C30") (pin "1") (pinfunction "1_1") (pintype "passive"))
      (node (ref "C31") (pin "1") (pinfunction "1_1") (pintype "passive"))
      (node (ref "C32") (pin "1") (pinfunction "1_1") (pintype "passive"))
      (node (ref "C33") (pin "1") (pinfunction "1_1") (pintype "passive"))
      (node (ref "C34") (pin "1") (pinfunction "1_1") (pintype "passive"))
      (node (ref "C35") (pin "1") (pinfunction "1_1") (pintype "passive"))
      (node (ref "C36") (pin "1") (pinfunction "1_1") (pintype "passive"))
      (node (ref "C37") (pin "1") (pinfunction "1_1") (pintype "passive"))
      (node (ref "C46") (pin "1") (pinfunction "1_1") (pintype "passive"))
      (node (ref "C47") (pin "1") (pinfunction "1_1") (pintype "passive"))
      (node (ref "C48") (pin "1") (pinfunction "1_1") (pintype "passive"))
      (node (ref "C50") (pin "1") (pinfunction "1_1") (pintype "passive"))
      (node (ref "C51") (pin "1") (pinfunction "1_1") (pintype "passive"))
      (node (ref "C71") (pin "1") (pinfunction "1_1") (pintype "passive"))
      (node (ref "D3") (pin "2") (pinfunction "K_2") (pintype "passive"))
      (node (ref "J6") (pin "16") (pinfunction "16_16") (pintype "passive"))
      (node (ref "J8") (pin "1") (pinfunction "1_1") (pintype "passive"))
      (node (ref "R32") (pin "1") (pinfunction "1_1") (pintype "passive"))
      (node (ref "R34") (pin "1") (pinfunction "1_1") (pintype "passive"))
      (node (ref "R36") (pin "1") (pinfunction "1_1") (pintype "passive"))
      (node (ref "R38") (pin "1") (pinfunction "1_1") (pintype "passive"))
      (node (ref "R39") (pin "1") (pinfunction "1_1") (pintype "passive"))
      (node (ref "R42") (pin "2") (pinfunction "2_2") (pintype "passive"))
      (node (ref "R43") (pin "2") (pinfunction "2_2") (pintype "passive"))
      (node (ref "U4") (pin "1") (pinfunction "VDDANA_1") (pintype "passive"))
      (node (ref "U4") (pin "2") (pinfunction "ADVREF_2") (pintype "passive"))
      (node (ref "U4") (pin "22") (pinfunction "VDDIO_4_22") (pintype "passive"))
      (node (ref "U4") (pin "36") (pinfunction "VDDIO_3_36") (pintype "passive"))
      (node (ref "U4") (pin "4") (pinfunction "AD12BVREF_4") (pintype "passive"))
      (node (ref "U4") (pin "45") (pinfunction "VDDBU_45") (pintype "passive"))
      (node (ref "U4") (pin "53") (pinfunction "VDDIN_53") (pintype "passive"))
      (node (ref "U4") (pin "60") (pinfunction "VDDIO_2_60") (pintype "passive"))
      (node (ref "U4") (pin "79") (pinfunction "VDDUTMI_79") (pintype "passive"))
      (node (ref "U4") (pin "88") (pinfunction "VDDIO_1_88") (pintype "passive"))
      (node (ref "U5") (pin "5") (pinfunction "VCC_5") (pintype "power_in"))
      (node (ref "U6") (pin "5") (pinfunction "VCC_5") (pintype "power_in"))
      (node (ref "U7") (pin "1") (pinfunction "VOUT_1") (pintype "passive"))
      (node (ref "U7") (pin "2") (pinfunction "VOUT_2") (pintype "passive"))
      (node (ref "U8") (pin "14") (pinfunction "VCC_14") (pintype "power_in"))
      (node (ref "Y2") (pin "4") (pinfunction "VDD_4") (pintype "power_in"))
    )
    (net (code "60") (name "VDD_MAIN_5V") (class "Default")
      (node (ref "C49") (pin "1") (pinfunction "1_1") (pintype "passive"))
      (node (ref "U7") (pin "4") (pinfunction "EN_4") (pintype "passive"))
      (node (ref "U7") (pin "6") (pinfunction "VIN_6") (pintype "passive"))
    )
    (net (code "61") (name "unconnected-(J6-Pad1)") (class "Default")
      (node (ref "J6") (pin "1") (pinfunction "1_1") (pintype "passive"))
    )
    (net (code "62") (name "unconnected-(J6-Pad7)") (class "Default")
      (node (ref "J6") (pin "7") (pinfunction "7_7") (pintype "passive"))
    )
    (net (code "63") (name "unconnected-(J6-Pad9)") (class "Default")
      (node (ref "J6") (pin "9") (pinfunction "9_9") (pintype "passive"))
    )
    (net (code "64") (name "unconnected-(J6-Pad11)") (class "Default")
      (node (ref "J6") (pin "11") (pinfunction "11_11") (pintype "passive"))
    )
    (net (code "65") (name "unconnected-(J6-Pad13)") (class "Default")
      (node (ref "J6") (pin "13") (pinfunction "13_13") (pintype "passive"))
    )
    (net (code "66") (name "unconnected-(J6-Pad15)") (class "Default")
      (node (ref "J6") (pin "15") (pinfunction "15_15") (pintype "passive"))
    )
    (net (code "67") (name "unconnected-(J10-ID-Pad4)") (class "Default")
      (node (ref "J10") (pin "4") (pinfunction "ID_4") (pintype "passive"))
    )
    (net (code "68") (name "unconnected-(U4-PA2{slash}PGMNOE-Pad28)") (class "Default")
      (node (ref "U4") (pin "28") (pinfunction "PA2/PGMNOE_28") (pintype "passive"))
    )
    (net (code "69") (name "unconnected-(U4-PA5{slash}PGMM1-Pad31)") (class "Default")
      (node (ref "U4") (pin "31") (pinfunction "PA5/PGMM1_31") (pintype "passive"))
    )
    (net (code "70") (name "unconnected-(U4-PA6{slash}PGMM2-Pad32)") (class "Default")
      (node (ref "U4") (pin "32") (pinfunction "PA6/PGMM2_32") (pintype "passive"))
    )
    (net (code "71") (name "unconnected-(U4-PA7{slash}PGMM3-Pad33)") (class "Default")
      (node (ref "U4") (pin "33") (pinfunction "PA7/PGMM3_33") (pintype "passive"))
    )
    (net (code "72") (name "unconnected-(U4-PA8{slash}PGMD0-Pad37)") (class "Default")
      (node (ref "U4") (pin "37") (pinfunction "PA8/PGMD0_37") (pintype "passive"))
    )
    (net (code "73") (name "unconnected-(U4-PA9{slash}PGMD1-Pad38)") (class "Default")
      (node (ref "U4") (pin "38") (pinfunction "PA9/PGMD1_38") (pintype "passive"))
    )
    (net (code "74") (name "unconnected-(U4-PA10{slash}PGMD2-Pad39)") (class "Default")
      (node (ref "U4") (pin "39") (pinfunction "PA10/PGMD2_39") (pintype "passive"))
    )
    (net (code "75") (name "unconnected-(U4-PA14{slash}PGMD6-Pad11)") (class "Default")
      (node (ref "U4") (pin "11") (pinfunction "PA14/PGMD6_11") (pintype "passive"))
    )
    (net (code "76") (name "unconnected-(U4-PA16{slash}PGMD8-Pad13)") (class "Default")
      (node (ref "U4") (pin "13") (pinfunction "PA16/PGMD8_13") (pintype "passive"))
    )
    (net (code "77") (name "unconnected-(U4-PA19{slash}PGMD11-Pad18)") (class "Default")
      (node (ref "U4") (pin "18") (pinfunction "PA19/PGMD11_18") (pintype "passive"))
    )
    (net (code "78") (name "unconnected-(U4-PA27-Pad96)") (class "Default")
      (node (ref "U4") (pin "96") (pinfunction "PA27_96") (pintype "passive"))
    )
    (net (code "79") (name "unconnected-(U4-PA30-Pad6)") (class "Default")
      (node (ref "U4") (pin "6") (pinfunction "PA30_6") (pintype "passive"))
    )
    (net (code "80") (name "unconnected-(U4-PB0-Pad90)") (class "Default")
      (node (ref "U4") (pin "90") (pinfunction "PB0_90") (pintype "passive"))
    )
    (net (code "81") (name "unconnected-(U4-PB1-Pad91)") (class "Default")
      (node (ref "U4") (pin "91") (pinfunction "PB1_91") (pintype "passive"))
    )
    (net (code "82") (name "unconnected-(U4-PB2-Pad92)") (class "Default")
      (node (ref "U4") (pin "92") (pinfunction "PB2_92") (pintype "passive"))
    )
    (net (code "83") (name "unconnected-(U4-PB3-Pad7)") (class "Default")
      (node (ref "U4") (pin "7") (pinfunction "PB3_7") (pintype "passive"))
    )
    (net (code "84") (name "unconnected-(U4-PB4-Pad8)") (class "Default")
      (node (ref "U4") (pin "8") (pinfunction "PB4_8") (pintype "passive"))
    )
    (net (code "85") (name "unconnected-(U4-PB5-Pad97)") (class "Default")
      (node (ref "U4") (pin "97") (pinfunction "PB5_97") (pintype "passive"))
    )
    (net (code "86") (name "unconnected-(U4-PB6-Pad98)") (class "Default")
      (node (ref "U4") (pin "98") (pinfunction "PB6_98") (pintype "passive"))
    )
    (net (code "87") (name "unconnected-(U4-PB8-Pad100)") (class "Default")
      (node (ref "U4") (pin "100") (pinfunction "PB8_100") (pintype "passive"))
    )
    (net (code "88") (name "unconnected-(U4-PB9-Pad71)") (class "Default")
      (node (ref "U4") (pin "71") (pinfunction "PB9_71") (pintype "passive"))
    )
    (net (code "89") (name "unconnected-(U4-PB10-Pad70)") (class "Default")
      (node (ref "U4") (pin "70") (pinfunction "PB10_70") (pintype "passive"))
    )
    (net (code "90") (name "unconnected-(U4-PB11-Pad93)") (class "Default")
      (node (ref "U4") (pin "93") (pinfunction "PB11_93") (pintype "passive"))
    )
    (net (code "91") (name "unconnected-(U4-PB12-Pad94)") (class "Default")
      (node (ref "U4") (pin "94") (pinfunction "PB12_94") (pintype "passive"))
    )
    (net (code "92") (name "unconnected-(U4-PB13-Pad95)") (class "Default")
      (node (ref "U4") (pin "95") (pinfunction "PB13_95") (pintype "passive"))
    )
    (net (code "93") (name "unconnected-(U4-PB14-Pad69)") (class "Default")
      (node (ref "U4") (pin "69") (pinfunction "PB14_69") (pintype "passive"))
    )
    (net (code "94") (name "unconnected-(U4-PB15-Pad16)") (class "Default")
      (node (ref "U4") (pin "16") (pinfunction "PB15_16") (pintype "passive"))
    )
    (net (code "95") (name "unconnected-(U4-PB16-Pad15)") (class "Default")
      (node (ref "U4") (pin "15") (pinfunction "PB16_15") (pintype "passive"))
    )
    (net (code "96") (name "unconnected-(U4-PB17-Pad68)") (class "Default")
      (node (ref "U4") (pin "68") (pinfunction "PB17_68") (pintype "passive"))
    )
    (net (code "97") (name "unconnected-(U4-PB18-Pad67)") (class "Default")
      (node (ref "U4") (pin "67") (pinfunction "PB18_67") (pintype "passive"))
    )
    (net (code "98") (name "unconnected-(U4-PB19-Pad66)") (class "Default")
      (node (ref "U4") (pin "66") (pinfunction "PB19_66") (pintype "passive"))
    )
    (net (code "99") (name "unconnected-(U4-PB20-Pad65)") (class "Default")
      (node (ref "U4") (pin "65") (pinfunction "PB20_65") (pintype "passive"))
    )
    (net (code "100") (name "unconnected-(U4-PB21-Pad64)") (class "Default")
      (node (ref "U4") (pin "64") (pinfunction "PB21_64") (pintype "passive"))
    )
    (net (code "101") (name "unconnected-(U4-PB22-Pad63)") (class "Default")
      (node (ref "U4") (pin "63") (pinfunction "PB22_63") (pintype "passive"))
    )
    (net (code "102") (name "unconnected-(U4-PB23-Pad62)") (class "Default")
      (node (ref "U4") (pin "62") (pinfunction "PB23_62") (pintype "passive"))
    )
    (net (code "103") (name "unconnected-(U4-PB24-Pad58)") (class "Default")
      (node (ref "U4") (pin "58") (pinfunction "PB24_58") (pintype "passive"))
    )
    (net (code "104") (name "unconnected-(U4-TEST-Pad44)") (class "Default")
      (node (ref "U4") (pin "44") (pinfunction "TEST_44") (pintype "passive"))
    )
    (net (code "105") (name "unconnected-(U4-XIN32-Pad50)") (class "Default")
      (node (ref "U4") (pin "50") (pinfunction "XIN32_50") (pintype "passive"))
    )
    (net (code "106") (name "unconnected-(U4-XOUT32-Pad49)") (class "Default")
      (node (ref "U4") (pin "49") (pinfunction "XOUT32_49") (pintype "passive"))
    )
    (net (code "107") (name "unconnected-(U7-NC-Pad5)") (class "Default")
      (node (ref "U7") (pin "5") (pinfunction "NC_5") (pintype "passive"))
    )
    (net (code "108") (name "unconnected-(U8-EP-Pad17)") (class "Default")
      (node (ref "U8") (pin "17") (pinfunction "EP_17") (pintype "passive"))
    )
    (net (code "109") (name "unconnected-(Y2-EN-Pad1)") (class "Default")
      (node (ref "Y2") (pin "1") (pinfunction "EN_1") (pintype "input"))
    )
  )
)
